# EasyEda_Pro_Project_file.net
KiCad netlist of a schematic drawn in EasyEDA Pro
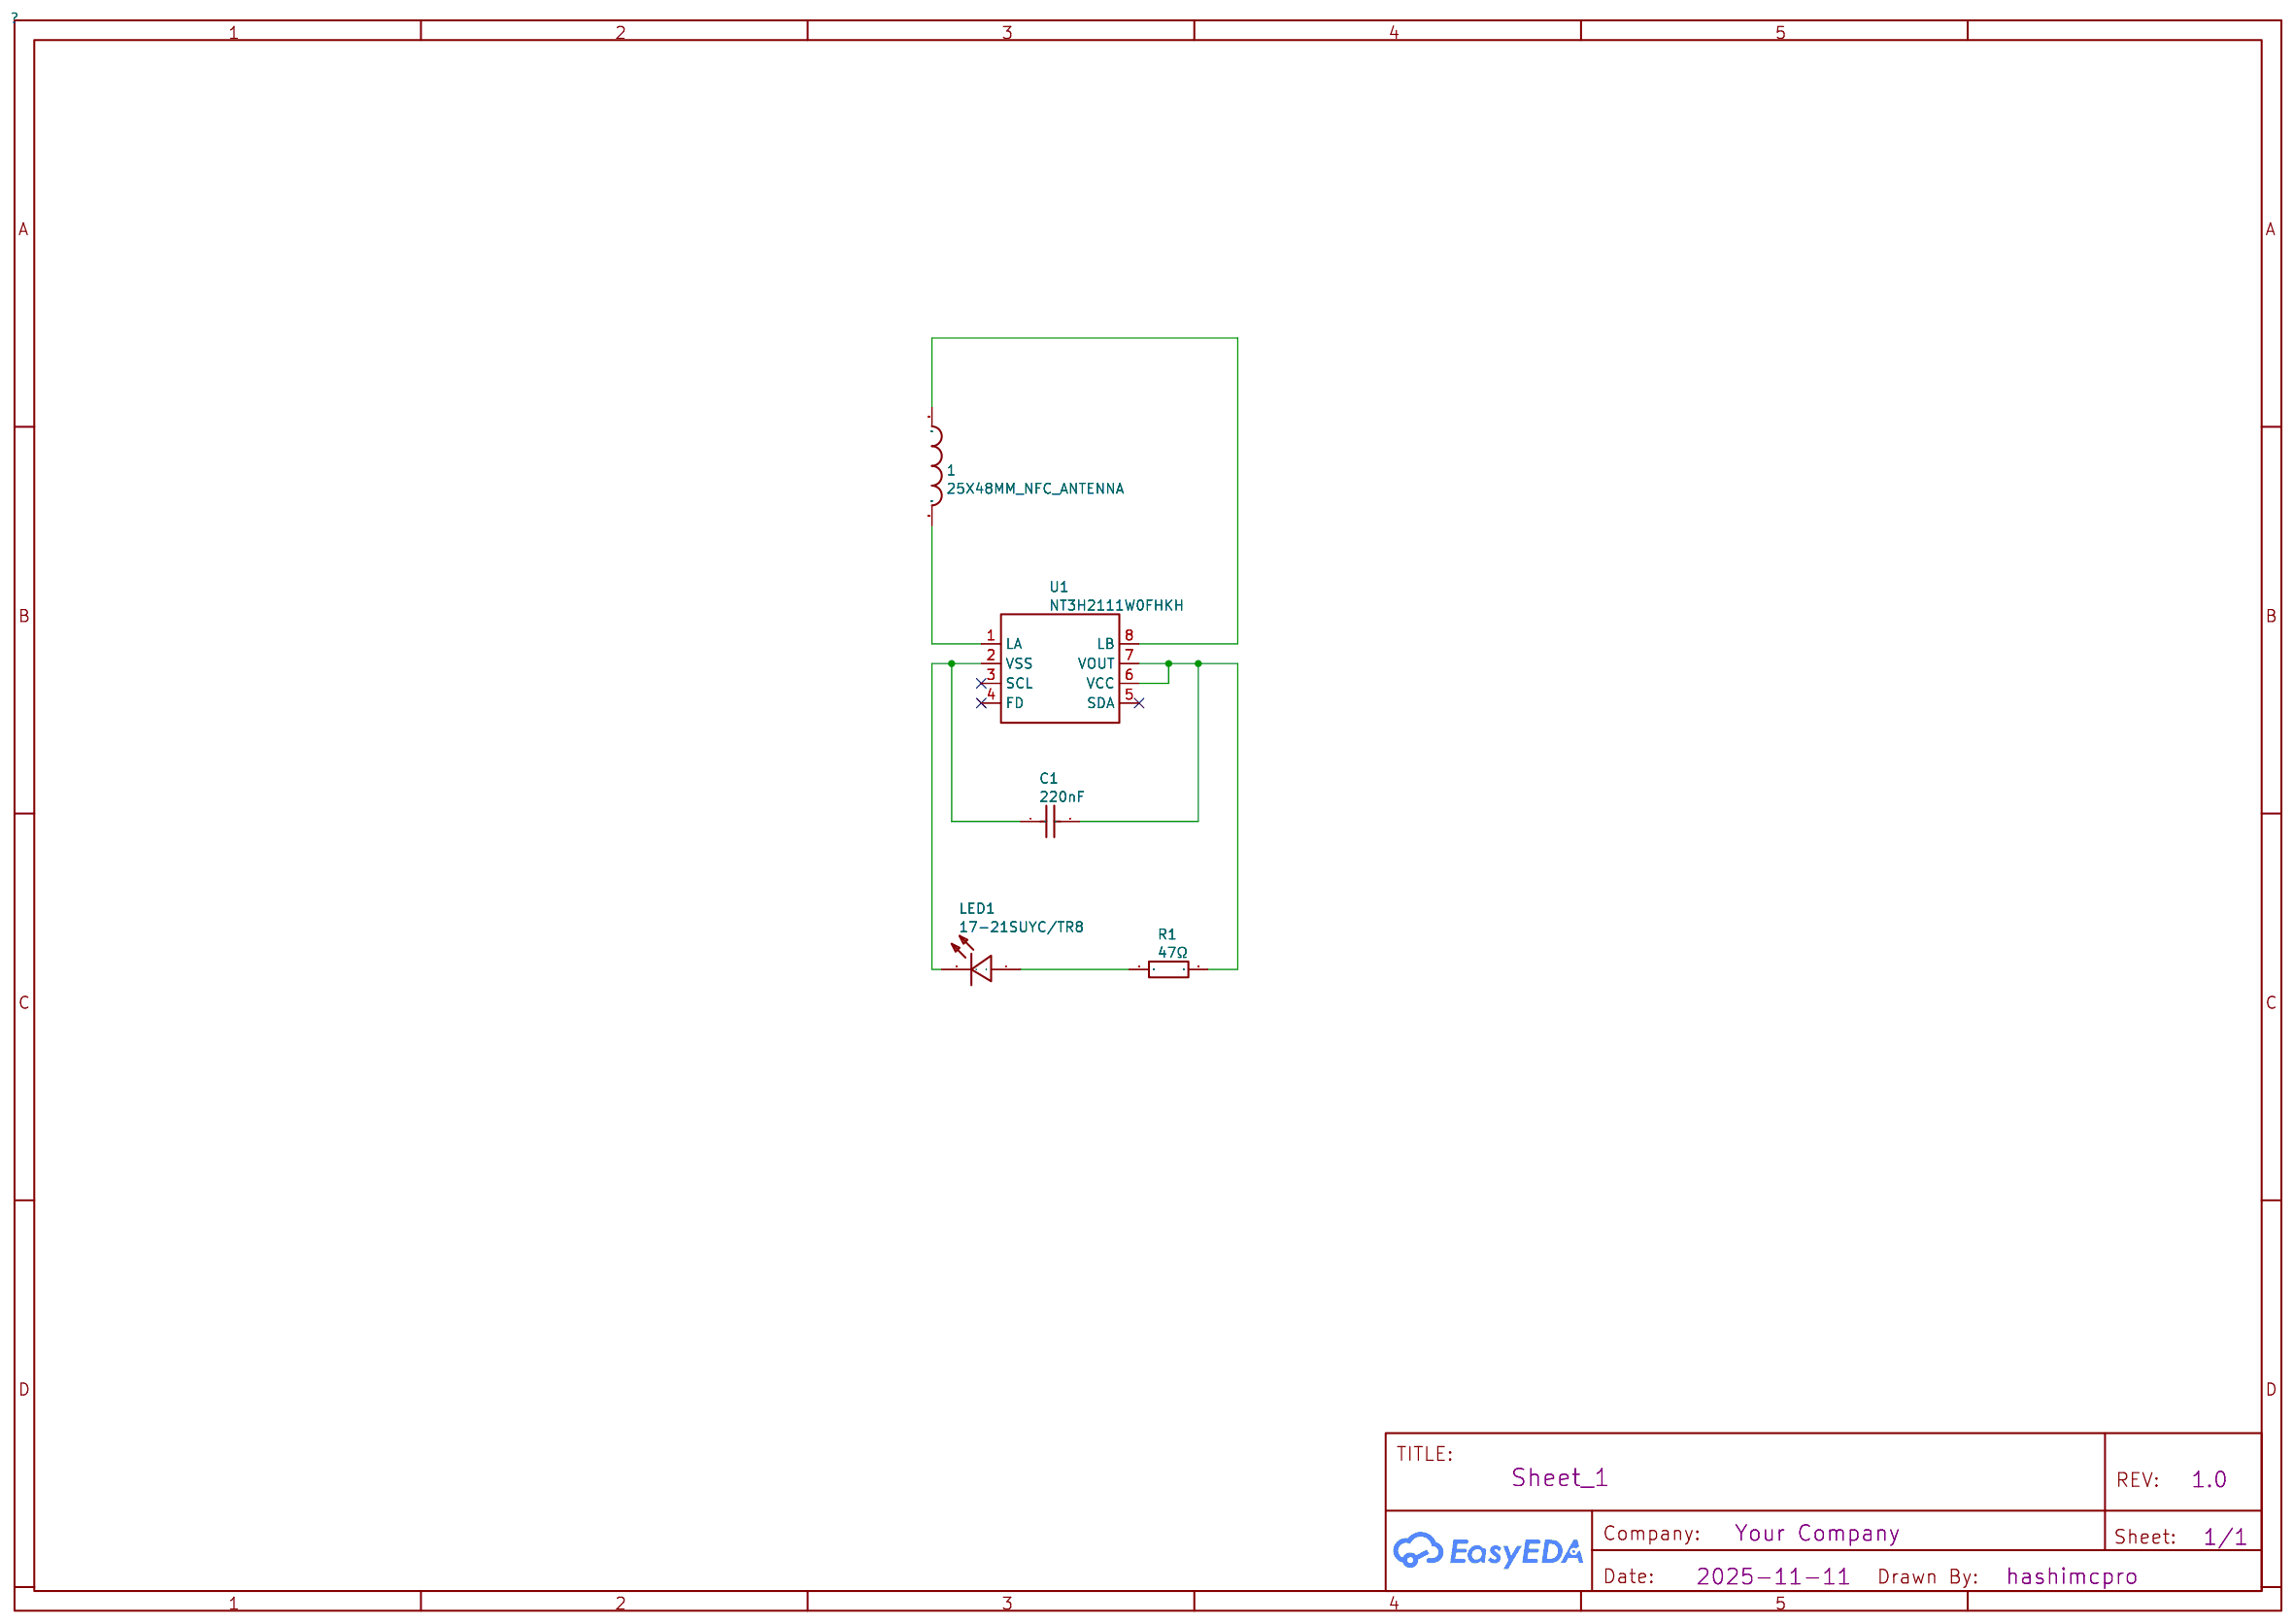
[diagram p0: schematic sheet]

(export (version "E")
  (design (tool "Eeschema 10.0.6"))
  (components
    (comp (ref "1")
      (value "25X48MM_NFC_ANTENNA")
      (footprint "easyedapro:25X48MM_NFC_ANTENNA")
      (fields (field (name "Contributor") "dnonoo"))
      (libsource (lib "easyedapro") (part "25X48MM_NFC_ANTENNA"))
    )
    (comp (ref "C1")
      (value "220nF")
      (footprint "easyedapro:C0603")
      (fields
        (field (name "Manufacturer Part") "CL10B224KA8NNNC")
        (field (name "Manufacturer") "SAMSUNG(三星)")
      )
      (libsource (lib "easyedapro") (part "220nF"))
    )
    (comp (ref "LED1")
      (value "17-21SUYC/TR8")
      (footprint "easyedapro:LED0805-R-RD")
      (fields (field (name "Manufacturer Part") "KT-0805黄灯") (field (name "Manufacturer") "KENTO"))
      (libsource (lib "easyedapro") (part "17-21SUYC/TR8"))
    )
    (comp (ref "R1")
      (value "47Ω")
      (footprint "easyedapro:R0603")
      (fields
        (field (name "Manufacturer Part") "0603WAF470JT5E")
        (field (name "Manufacturer") "UNI-ROYAL(厚声)")
      )
      (libsource (lib "easyedapro") (part "47Ω"))
    )
    (comp (ref "U1")
      (value "NT3H2111W0FHKH")
      (footprint "easyedapro:XQFN-8_L1.6-W1.6-P0.50-BL_NT3H2111W0FHKH")
      (fields (field (name "Manufacturer") "NXP(恩智浦)") (field (name "Contributor") "LCSC"))
      (libsource (lib "easyedapro") (part "NT3H2111W0FHKH"))
    )
  )
  (nets
    (net (code "1") (name "Net-(LED1-+)") (class "Default")
      (node (ref "LED1") (pin "1") (pinfunction "+_1") (pintype "unspecified"))
      (node (ref "R1") (pin "1") (pinfunction "1_1") (pintype "input"))
    )
    (net (code "2") (name "Net-(LED1--)") (class "Default")
      (node (ref "C1") (pin "1") (pinfunction "1_1") (pintype "input"))
      (node (ref "LED1") (pin "2") (pinfunction "-_2") (pintype "unspecified"))
      (node (ref "U1") (pin "2") (pinfunction "VSS_2") (pintype "unspecified"))
    )
    (net (code "3") (name "Net-(U1-LA)") (class "Default")
      (node (ref "1") (pin "P$2") (pinfunction "P$2_P$2") (pintype "bidirectional"))
      (node (ref "U1") (pin "1") (pinfunction "LA_1") (pintype "unspecified"))
    )
    (net (code "4") (name "Net-(U1-LB)") (class "Default")
      (node (ref "1") (pin "P$1") (pinfunction "P$1_P$1") (pintype "bidirectional"))
      (node (ref "U1") (pin "8") (pinfunction "LB_8") (pintype "unspecified"))
    )
    (net (code "5") (name "Net-(U1-VCC)") (class "Default")
      (node (ref "C1") (pin "2") (pinfunction "2_2") (pintype "input"))
      (node (ref "R1") (pin "2") (pinfunction "2_2") (pintype "input"))
      (node (ref "U1") (pin "6") (pinfunction "VCC_6") (pintype "unspecified"))
      (node (ref "U1") (pin "7") (pinfunction "VOUT_7") (pintype "unspecified"))
    )
    (net (code "6") (name "unconnected-(U1-FD-Pad4)") (class "Default")
      (node (ref "U1") (pin "4") (pinfunction "FD_4") (pintype "unspecified+no_connect"))
    )
    (net (code "7") (name "unconnected-(U1-SCL-Pad3)") (class "Default")
      (node (ref "U1") (pin "3") (pinfunction "SCL_3") (pintype "unspecified+no_connect"))
    )
    (net (code "8") (name "unconnected-(U1-SDA-Pad5)") (class "Default")
      (node (ref "U1") (pin "5") (pinfunction "SDA_5") (pintype "unspecified+no_connect"))
    )
  )
)
